# iot.net
KiCad netlist of a schematic drawn in EAGLE
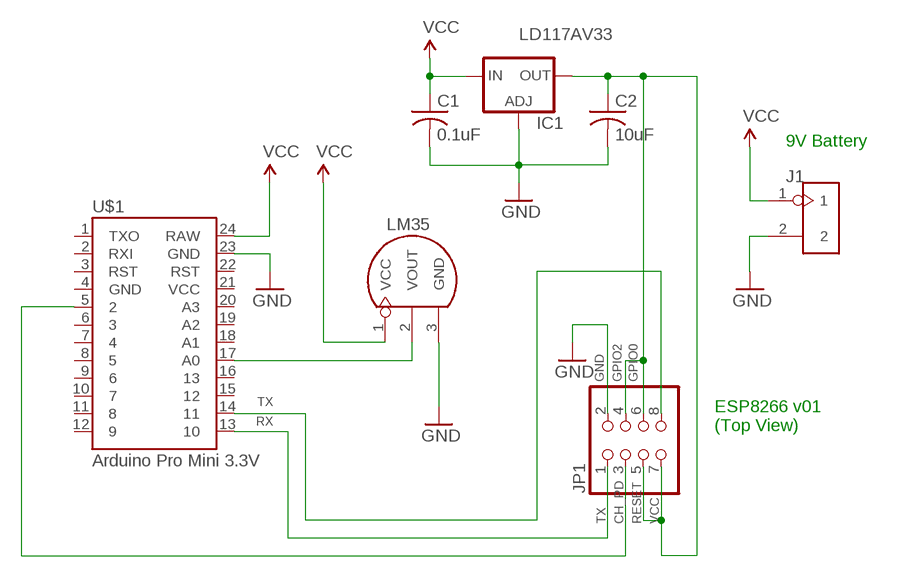
[diagram p0: schematic, sheet 1]

(export (version "E")
  (design (tool "Eeschema 10.0.6"))
  (components
    (comp (ref "C1")
      (value "0.1uF")
      (footprint "eagle-import:C025-024X044")
      (libsource (lib "eagle-import") (part "C-US025-024X044"))
    )
    (comp (ref "C2")
      (value "10uF")
      (footprint "eagle-import:C025-024X044")
      (libsource (lib "eagle-import") (part "C-US025-024X044"))
    )
    (comp (ref "IC1")
      (value "LD117AV33")
      (footprint "eagle-import:TO220L1")
      (libsource (lib "eagle-import") (part "LD117A?V33"))
    )
    (comp (ref "J1")
      (value "HEADER-2P-1.5")
      (footprint "eagle-import:2P-1.5")
      (libsource (lib "eagle-import") (part "HEADER-2P-1.5"))
    )
    (comp (ref "JP1")
      (value "PINHD-2X4")
      (footprint "eagle-import:2X04")
      (libsource (lib "eagle-import") (part "PINHD-2X4"))
    )
    (comp (ref "LM35")
      (value "SENSOR-LM35")
      (footprint "eagle-import:TO-92")
      (libsource (lib "eagle-import") (part "SENSOR-LM35"))
    )
    (comp (ref "U$1")
      (value "Arduino Pro Mini 3.3V")
      (footprint "eagle-import:ARDUINO_MINI")
      (libsource (lib "eagle-import") (part "ARDUINO_MINI"))
    )
  )
  (nets
    (net (code "1") (name "GND") (class "Default")
      (node (ref "C1") (pin "2") (pinfunction "2_2") (pintype "passive"))
      (node (ref "C2") (pin "2") (pinfunction "2_2") (pintype "passive"))
      (node (ref "IC1") (pin "1") (pinfunction "ADJ_1") (pintype "input"))
      (node (ref "J1") (pin "2") (pinfunction "2_2") (pintype "bidirectional"))
      (node (ref "JP1") (pin "2") (pinfunction "2_2") (pintype "passive"))
      (node (ref "LM35") (pin "3") (pinfunction "GND_3") (pintype "bidirectional"))
      (node (ref "U$1") (pin "23") (pinfunction "GND_23") (pintype "bidirectional"))
    )
    (net (code "2") (name "Net-(IC1-OUT)") (class "Default")
      (node (ref "C2") (pin "1") (pinfunction "1_1") (pintype "passive"))
      (node (ref "IC1") (pin "2") (pinfunction "OUT_2") (pintype "passive"))
      (node (ref "JP1") (pin "4") (pinfunction "4_4") (pintype "passive"))
      (node (ref "JP1") (pin "5") (pinfunction "5_5") (pintype "passive"))
      (node (ref "JP1") (pin "6") (pinfunction "6_6") (pintype "passive"))
      (node (ref "JP1") (pin "7") (pinfunction "7_7") (pintype "passive"))
    )
    (net (code "3") (name "Net-(LM35-VOUT)") (class "Default")
      (node (ref "LM35") (pin "2") (pinfunction "VOUT_2") (pintype "bidirectional"))
      (node (ref "U$1") (pin "17") (pinfunction "A0_17") (pintype "bidirectional"))
    )
    (net (code "4") (name "Net-(U$1-2)") (class "Default")
      (node (ref "JP1") (pin "3") (pinfunction "3_3") (pintype "passive"))
      (node (ref "U$1") (pin "5") (pinfunction "2_5") (pintype "bidirectional"))
    )
    (net (code "5") (name "Net-(U$1-10)") (class "Default")
      (node (ref "JP1") (pin "1") (pinfunction "1_1") (pintype "passive"))
      (node (ref "U$1") (pin "13") (pinfunction "10_13") (pintype "bidirectional"))
    )
    (net (code "6") (name "Net-(U$1-11)") (class "Default")
      (node (ref "JP1") (pin "8") (pinfunction "8_8") (pintype "passive"))
      (node (ref "U$1") (pin "14") (pinfunction "11_14") (pintype "bidirectional"))
    )
    (net (code "7") (name "VCC") (class "Default")
      (node (ref "C1") (pin "1") (pinfunction "1_1") (pintype "passive"))
      (node (ref "IC1") (pin "3") (pinfunction "IN_3") (pintype "input"))
      (node (ref "J1") (pin "1") (pinfunction "1_1") (pintype "bidirectional"))
      (node (ref "LM35") (pin "1") (pinfunction "VCC_1") (pintype "bidirectional"))
      (node (ref "U$1") (pin "24") (pinfunction "RAW_24") (pintype "bidirectional"))
    )
    (net (code "8") (name "unconnected-(U$1-3-Pad6)") (class "Default")
      (node (ref "U$1") (pin "6") (pinfunction "3_6") (pintype "bidirectional"))
    )
    (net (code "9") (name "unconnected-(U$1-4-Pad7)") (class "Default")
      (node (ref "U$1") (pin "7") (pinfunction "4_7") (pintype "bidirectional"))
    )
    (net (code "10") (name "unconnected-(U$1-5-Pad8)") (class "Default")
      (node (ref "U$1") (pin "8") (pinfunction "5_8") (pintype "bidirectional"))
    )
    (net (code "11") (name "unconnected-(U$1-6-Pad9)") (class "Default")
      (node (ref "U$1") (pin "9") (pinfunction "6_9") (pintype "bidirectional"))
    )
    (net (code "12") (name "unconnected-(U$1-7-Pad10)") (class "Default")
      (node (ref "U$1") (pin "10") (pinfunction "7_10") (pintype "bidirectional"))
    )
    (net (code "13") (name "unconnected-(U$1-8-Pad11)") (class "Default")
      (node (ref "U$1") (pin "11") (pinfunction "8_11") (pintype "bidirectional"))
    )
    (net (code "14") (name "unconnected-(U$1-9-Pad12)") (class "Default")
      (node (ref "U$1") (pin "12") (pinfunction "9_12") (pintype "bidirectional"))
    )
    (net (code "15") (name "unconnected-(U$1-12-Pad15)") (class "Default")
      (node (ref "U$1") (pin "15") (pinfunction "12_15") (pintype "bidirectional"))
    )
    (net (code "16") (name "unconnected-(U$1-13-Pad16)") (class "Default")
      (node (ref "U$1") (pin "16") (pinfunction "13_16") (pintype "bidirectional"))
    )
    (net (code "17") (name "unconnected-(U$1-A1-Pad18)") (class "Default")
      (node (ref "U$1") (pin "18") (pinfunction "A1_18") (pintype "bidirectional"))
    )
    (net (code "18") (name "unconnected-(U$1-A2-Pad19)") (class "Default")
      (node (ref "U$1") (pin "19") (pinfunction "A2_19") (pintype "bidirectional"))
    )
    (net (code "19") (name "unconnected-(U$1-A3-Pad20)") (class "Default")
      (node (ref "U$1") (pin "20") (pinfunction "A3_20") (pintype "bidirectional"))
    )
    (net (code "20") (name "unconnected-(U$1-GND-Pad4)") (class "Default")
      (node (ref "U$1") (pin "4") (pinfunction "GND_4") (pintype "bidirectional"))
    )
    (net (code "21") (name "unconnected-(U$1-RST-Pad3)") (class "Default")
      (node (ref "U$1") (pin "3") (pinfunction "RST_3") (pintype "bidirectional"))
    )
    (net (code "22") (name "unconnected-(U$1-RST-Pad22)") (class "Default")
      (node (ref "U$1") (pin "22") (pinfunction "RST_22") (pintype "bidirectional"))
    )
    (net (code "23") (name "unconnected-(U$1-RXI-Pad2)") (class "Default")
      (node (ref "U$1") (pin "2") (pinfunction "RXI_2") (pintype "bidirectional"))
    )
    (net (code "24") (name "unconnected-(U$1-TXO-Pad1)") (class "Default")
      (node (ref "U$1") (pin "1") (pinfunction "TXO_1") (pintype "bidirectional"))
    )
    (net (code "25") (name "unconnected-(U$1-VCC-Pad21)") (class "Default")
      (node (ref "U$1") (pin "21") (pinfunction "VCC_21") (pintype "bidirectional"))
    )
  )
)
